# clock.net
KiCad netlist of a schematic drawn in EAGLE
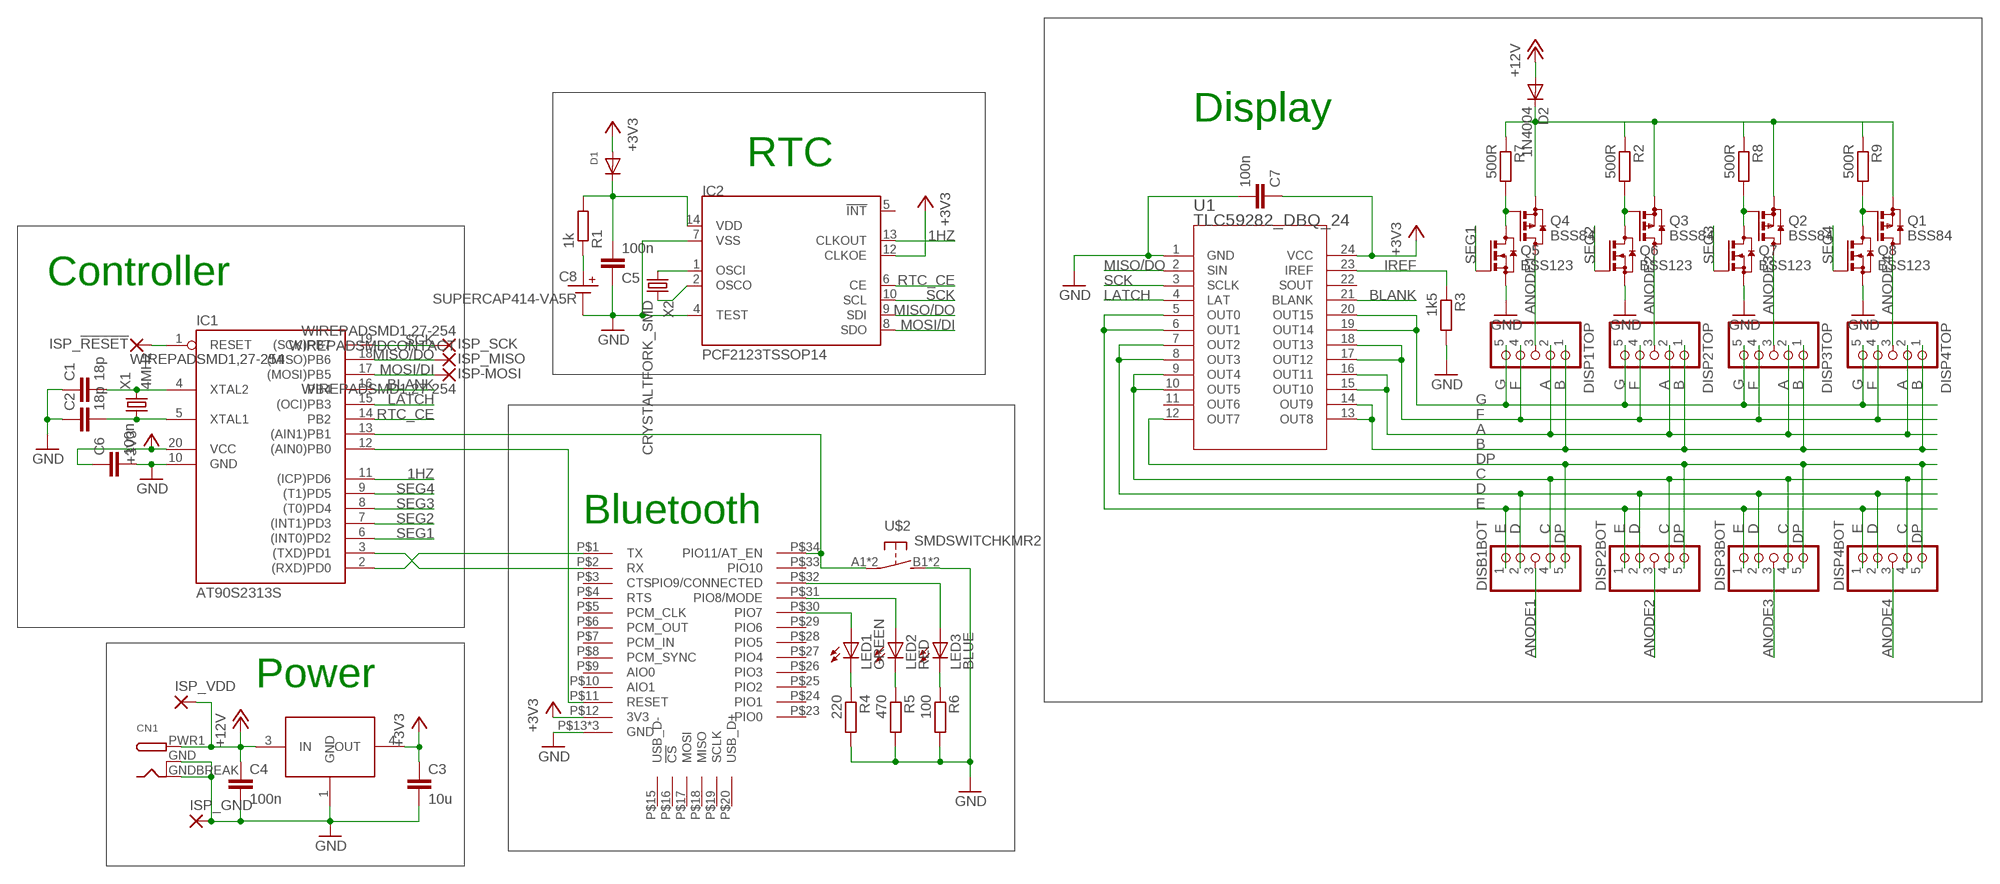
[diagram p0: schematic, sheet 1]

(export (version "E")
  (design (tool "Eeschema 10.0.6"))
  (components
    (comp (ref "C1")
      (value "18p")
      (footprint "eagle-import:C0603K")
      (libsource (lib "eagle-import") (part "C-EUC0603K"))
    )
    (comp (ref "C2")
      (value "18p")
      (footprint "eagle-import:C0603K")
      (libsource (lib "eagle-import") (part "C-EUC0603K"))
    )
    (comp (ref "C3")
      (value "10u")
      (footprint "eagle-import:C0805K")
      (libsource (lib "eagle-import") (part "C-EUC0805K"))
    )
    (comp (ref "C4")
      (value "100n")
      (footprint "eagle-import:C0603K")
      (libsource (lib "eagle-import") (part "C-EUC0603K"))
    )
    (comp (ref "C5")
      (value "100n")
      (footprint "eagle-import:C0603K")
      (libsource (lib "eagle-import") (part "C-EUC0603K"))
    )
    (comp (ref "C6")
      (value "100n")
      (footprint "eagle-import:C0603K")
      (libsource (lib "eagle-import") (part "C-EUC0603K"))
    )
    (comp (ref "C7")
      (value "100n")
      (footprint "eagle-import:C0603K")
      (libsource (lib "eagle-import") (part "C-EUC0603K"))
    )
    (comp (ref "C8")
      (value "SUPERCAP414-VA5R")
      (footprint "eagle-import:414-VA5R")
      (libsource (lib "eagle-import") (part "SUPERCAP414-VA5R"))
    )
    (comp (ref "CN1")
      (value "DCBARRELSMT")
      (footprint "eagle-import:DCJACK_2MM_SMT")
      (libsource (lib "eagle-import") (part "DCBARRELSMT"))
    )
    (comp (ref "D1")
      (value "DIODESOD-523")
      (footprint "eagle-import:SOD-523")
      (libsource (lib "eagle-import") (part "DIODESOD-523"))
    )
    (comp (ref "D2")
      (value "1N4004")
      (footprint "eagle-import:DO41-10")
      (libsource (lib "eagle-import") (part "1N4004"))
    )
    (comp (ref "DISB1BOT")
      (value "PINHD-1X5")
      (footprint "eagle-import:1X05WIDE")
      (libsource (lib "eagle-import") (part "PINHD-1X5"))
    )
    (comp (ref "DISP1TOP")
      (value "PINHD-1X5")
      (footprint "eagle-import:1X05WIDE")
      (libsource (lib "eagle-import") (part "PINHD-1X5"))
    )
    (comp (ref "DISP2BOT")
      (value "PINHD-1X5")
      (footprint "eagle-import:1X05WIDE")
      (libsource (lib "eagle-import") (part "PINHD-1X5"))
    )
    (comp (ref "DISP2TOP")
      (value "PINHD-1X5")
      (footprint "eagle-import:1X05WIDE")
      (libsource (lib "eagle-import") (part "PINHD-1X5"))
    )
    (comp (ref "DISP3BOT")
      (value "PINHD-1X5")
      (footprint "eagle-import:1X05WIDE")
      (libsource (lib "eagle-import") (part "PINHD-1X5"))
    )
    (comp (ref "DISP3TOP")
      (value "PINHD-1X5")
      (footprint "eagle-import:1X05WIDE")
      (libsource (lib "eagle-import") (part "PINHD-1X5"))
    )
    (comp (ref "DISP4BOT")
      (value "PINHD-1X5")
      (footprint "eagle-import:1X05WIDE")
      (libsource (lib "eagle-import") (part "PINHD-1X5"))
    )
    (comp (ref "DISP4TOP")
      (value "PINHD-1X5")
      (footprint "eagle-import:1X05WIDE")
      (libsource (lib "eagle-import") (part "PINHD-1X5"))
    )
    (comp (ref "IC1")
      (value "AT90S2313S")
      (footprint "eagle-import:SO20L")
      (libsource (lib "eagle-import") (part "AT90S2313S"))
    )
    (comp (ref "IC2")
      (value "PCF2123TSSOP14")
      (footprint "eagle-import:TSSOP14")
      (libsource (lib "eagle-import") (part "PCF2123TSSOP14"))
    )
    (comp (ref "ISP-MOSI")
      (value "WIREPADSMD1,27-254")
      (footprint "eagle-import:SMD1,27-2,54")
      (libsource (lib "eagle-import") (part "WIREPADSMD1,27-254"))
    )
    (comp (ref "ISP_!RESET")
      (value "WIREPADSMD1,27-254")
      (footprint "eagle-import:SMD1,27-2,54")
      (libsource (lib "eagle-import") (part "WIREPADSMD1,27-254"))
    )
    (comp (ref "ISP_GND")
      (value "WIREPADSMD2,54-2,54")
      (footprint "eagle-import:SMD2,54-2,54")
      (libsource (lib "eagle-import") (part "WIREPADSMD2,54-2,54"))
    )
    (comp (ref "ISP_MISO")
      (value "WIREPADSMDCONTACT")
      (footprint "eagle-import:SMDCONTACT")
      (libsource (lib "eagle-import") (part "WIREPADSMDCONTACT"))
    )
    (comp (ref "ISP_SCK")
      (value "WIREPADSMD1,27-254")
      (footprint "eagle-import:SMD1,27-2,54")
      (libsource (lib "eagle-import") (part "WIREPADSMD1,27-254"))
    )
    (comp (ref "ISP_VDD")
      (value "WIREPADSMD2,54-2,54")
      (footprint "eagle-import:SMD2,54-2,54")
      (libsource (lib "eagle-import") (part "WIREPADSMD2,54-2,54"))
    )
    (comp (ref "LED1")
      (value "GREEN")
      (footprint "eagle-import:CHIPLED_0805")
      (libsource (lib "eagle-import") (part "LEDCHIPLED_0805"))
    )
    (comp (ref "LED2")
      (value "RED")
      (footprint "eagle-import:CHIPLED_0805")
      (libsource (lib "eagle-import") (part "LEDCHIPLED_0805"))
    )
    (comp (ref "LED3")
      (value "BLUE")
      (footprint "eagle-import:CHIPLED_0805")
      (libsource (lib "eagle-import") (part "LEDCHIPLED_0805"))
    )
    (comp (ref "Q1")
      (value "BSS84")
      (footprint "eagle-import:SOT23")
      (libsource (lib "eagle-import") (part "BSS84"))
    )
    (comp (ref "Q2")
      (value "BSS84")
      (footprint "eagle-import:SOT23")
      (libsource (lib "eagle-import") (part "BSS84"))
    )
    (comp (ref "Q3")
      (value "BSS84")
      (footprint "eagle-import:SOT23")
      (libsource (lib "eagle-import") (part "BSS84"))
    )
    (comp (ref "Q4")
      (value "BSS84")
      (footprint "eagle-import:SOT23")
      (libsource (lib "eagle-import") (part "BSS84"))
    )
    (comp (ref "Q5")
      (value "BSS123")
      (footprint "eagle-import:SOT23")
      (libsource (lib "eagle-import") (part "BSS123"))
    )
    (comp (ref "Q6")
      (value "BSS123")
      (footprint "eagle-import:SOT23")
      (libsource (lib "eagle-import") (part "BSS123"))
    )
    (comp (ref "Q7")
      (value "BSS123")
      (footprint "eagle-import:SOT23")
      (libsource (lib "eagle-import") (part "BSS123"))
    )
    (comp (ref "Q8")
      (value "BSS123")
      (footprint "eagle-import:SOT23")
      (libsource (lib "eagle-import") (part "BSS123"))
    )
    (comp (ref "R1")
      (value "1k")
      (footprint "eagle-import:R0603")
      (libsource (lib "eagle-import") (part "R-EU_R0603"))
    )
    (comp (ref "R2")
      (value "500R")
      (footprint "eagle-import:R0603")
      (libsource (lib "eagle-import") (part "R-EU_R0603"))
    )
    (comp (ref "R3")
      (value "1k5")
      (footprint "eagle-import:R0603")
      (libsource (lib "eagle-import") (part "R-EU_R0603"))
    )
    (comp (ref "R4")
      (value "220")
      (footprint "eagle-import:R0603")
      (libsource (lib "eagle-import") (part "R-EU_R0603"))
    )
    (comp (ref "R5")
      (value "470")
      (footprint "eagle-import:R0603")
      (libsource (lib "eagle-import") (part "R-EU_R0603"))
    )
    (comp (ref "R6")
      (value "100")
      (footprint "eagle-import:R0603")
      (libsource (lib "eagle-import") (part "R-EU_R0603"))
    )
    (comp (ref "R7")
      (value "500R")
      (footprint "eagle-import:R0603")
      (libsource (lib "eagle-import") (part "R-EU_R0603"))
    )
    (comp (ref "R8")
      (value "500R")
      (footprint "eagle-import:R0603")
      (libsource (lib "eagle-import") (part "R-EU_R0603"))
    )
    (comp (ref "R9")
      (value "500R")
      (footprint "eagle-import:R0603")
      (libsource (lib "eagle-import") (part "R-EU_R0603"))
    )
    (comp (ref "U$1")
      (value "BT-HC-05")
      (footprint "eagle-import:BT-HC-05")
      (libsource (lib "eagle-import") (part "BT-HC-05"))
    )
    (comp (ref "U$2")
      (value "SMDSWITCHKMR2")
      (footprint "eagle-import:KMR2")
      (libsource (lib "eagle-import") (part "SMDSWITCHKMR2"))
    )
    (comp (ref "U$3")
      (value "REGULATORDPAK")
      (footprint "eagle-import:DPAK")
      (libsource (lib "eagle-import") (part "REGULATORDPAK"))
    )
    (comp (ref "U1")
      (value "TLC59282_DBQ_24")
      (footprint "eagle-import:DBQ24")
      (fields
        (field (name "GENERIC_PART_NUMBER") "TLC59282")
        (field (name "MANUFACTURER") "Texas Instruments")
        (field (name "MANUFACTURER_PART_NUMBER") "tlc59282_dbq_24")
      )
      (libsource (lib "eagle-import") (part "TLC59282_DBQ_24"))
    )
    (comp (ref "X1")
      (value "4MHz")
      (footprint "eagle-import:HC49UP")
      (libsource (lib "eagle-import") (part "CRYSTALHC49UP"))
    )
    (comp (ref "X2")
      (value "CRYSTALTFORK_SMD")
      (footprint "eagle-import:TFORK_SMD")
      (libsource (lib "eagle-import") (part "CRYSTALTFORK_SMD"))
    )
  )
  (nets
    (net (code "1") (name "+3V3") (class "Default")
      (node (ref "C3") (pin "1") (pinfunction "1_1") (pintype "passive"))
      (node (ref "C6") (pin "1") (pinfunction "1_1") (pintype "passive"))
      (node (ref "C7") (pin "1") (pinfunction "1_1") (pintype "passive"))
      (node (ref "D1") (pin "A") (pinfunction "A_A") (pintype "passive"))
      (node (ref "IC1") (pin "20") (pinfunction "VCC_20") (pintype "power_in"))
      (node (ref "IC2") (pin "12") (pinfunction "CLKOE_12") (pintype "input"))
      (node (ref "U$1") (pin "P$12") (pinfunction "3V3_P$12") (pintype "bidirectional"))
      (node (ref "U$3") (pin "4") (pinfunction "OUT_4") (pintype "bidirectional"))
      (node (ref "U1") (pin "24") (pinfunction "VCC_24") (pintype "power_in"))
    )
    (net (code "2") (name "+12V") (class "Default")
      (node (ref "C4") (pin "1") (pinfunction "1_1") (pintype "passive"))
      (node (ref "CN1") (pin "PWR1") (pinfunction "PWR_PWR1") (pintype "power_in"))
      (node (ref "D2") (pin "A") (pinfunction "A_A") (pintype "passive"))
      (node (ref "ISP_VDD") (pin "1") (pinfunction "P_1") (pintype "passive"))
      (node (ref "U$3") (pin "3") (pinfunction "IN_3") (pintype "bidirectional"))
    )
    (net (code "3") (name "/1HZ") (class "Default")
      (node (ref "IC1") (pin "11") (pinfunction "(ICP)PD6_11") (pintype "bidirectional"))
      (node (ref "IC2") (pin "13") (pinfunction "CLKOUT_13") (pintype "output"))
    )
    (net (code "4") (name "/A") (class "Default")
      (node (ref "DISP1TOP") (pin "2") (pinfunction "2_2") (pintype "passive"))
      (node (ref "DISP2TOP") (pin "2") (pinfunction "2_2") (pintype "passive"))
      (node (ref "DISP3TOP") (pin "2") (pinfunction "2_2") (pintype "passive"))
      (node (ref "DISP4TOP") (pin "2") (pinfunction "2_2") (pintype "passive"))
      (node (ref "U1") (pin "15") (pinfunction "OUT10_15") (pintype "output"))
      (node (ref "U1") (pin "16") (pinfunction "OUT11_16") (pintype "output"))
    )
    (net (code "5") (name "/ANODE1") (class "Default")
      (node (ref "DISB1BOT") (pin "3") (pinfunction "3_3") (pintype "passive"))
      (node (ref "DISP1TOP") (pin "3") (pinfunction "3_3") (pintype "passive"))
      (node (ref "Q4") (pin "3") (pinfunction "D_3") (pintype "passive"))
    )
    (net (code "6") (name "/ANODE2") (class "Default")
      (node (ref "DISP2BOT") (pin "3") (pinfunction "3_3") (pintype "passive"))
      (node (ref "DISP2TOP") (pin "3") (pinfunction "3_3") (pintype "passive"))
      (node (ref "Q3") (pin "3") (pinfunction "D_3") (pintype "passive"))
    )
    (net (code "7") (name "/ANODE3") (class "Default")
      (node (ref "DISP3BOT") (pin "3") (pinfunction "3_3") (pintype "passive"))
      (node (ref "DISP3TOP") (pin "3") (pinfunction "3_3") (pintype "passive"))
      (node (ref "Q2") (pin "3") (pinfunction "D_3") (pintype "passive"))
    )
    (net (code "8") (name "/ANODE4") (class "Default")
      (node (ref "DISP4BOT") (pin "3") (pinfunction "3_3") (pintype "passive"))
      (node (ref "DISP4TOP") (pin "3") (pinfunction "3_3") (pintype "passive"))
      (node (ref "Q1") (pin "3") (pinfunction "D_3") (pintype "passive"))
    )
    (net (code "9") (name "/B") (class "Default")
      (node (ref "DISP1TOP") (pin "1") (pinfunction "1_1") (pintype "passive"))
      (node (ref "DISP2TOP") (pin "1") (pinfunction "1_1") (pintype "passive"))
      (node (ref "DISP3TOP") (pin "1") (pinfunction "1_1") (pintype "passive"))
      (node (ref "DISP4TOP") (pin "1") (pinfunction "1_1") (pintype "passive"))
      (node (ref "U1") (pin "13") (pinfunction "OUT8_13") (pintype "output"))
      (node (ref "U1") (pin "14") (pinfunction "OUT9_14") (pintype "output"))
    )
    (net (code "10") (name "/BLANK") (class "Default")
      (node (ref "IC1") (pin "16") (pinfunction "PB4_16") (pintype "bidirectional"))
      (node (ref "U1") (pin "21") (pinfunction "BLANK_21") (pintype "input"))
    )
    (net (code "11") (name "/C") (class "Default")
      (node (ref "DISB1BOT") (pin "4") (pinfunction "4_4") (pintype "passive"))
      (node (ref "DISP2BOT") (pin "4") (pinfunction "4_4") (pintype "passive"))
      (node (ref "DISP3BOT") (pin "4") (pinfunction "4_4") (pintype "passive"))
      (node (ref "DISP4BOT") (pin "4") (pinfunction "4_4") (pintype "passive"))
      (node (ref "U1") (pin "10") (pinfunction "OUT5_10") (pintype "output"))
      (node (ref "U1") (pin "9") (pinfunction "OUT4_9") (pintype "output"))
    )
    (net (code "12") (name "/D") (class "Default")
      (node (ref "DISB1BOT") (pin "2") (pinfunction "2_2") (pintype "passive"))
      (node (ref "DISP2BOT") (pin "2") (pinfunction "2_2") (pintype "passive"))
      (node (ref "DISP3BOT") (pin "2") (pinfunction "2_2") (pintype "passive"))
      (node (ref "DISP4BOT") (pin "2") (pinfunction "2_2") (pintype "passive"))
      (node (ref "U1") (pin "7") (pinfunction "OUT2_7") (pintype "output"))
      (node (ref "U1") (pin "8") (pinfunction "OUT3_8") (pintype "output"))
    )
    (net (code "13") (name "/DP") (class "Default")
      (node (ref "DISB1BOT") (pin "5") (pinfunction "5_5") (pintype "passive"))
      (node (ref "DISP2BOT") (pin "5") (pinfunction "5_5") (pintype "passive"))
      (node (ref "DISP3BOT") (pin "5") (pinfunction "5_5") (pintype "passive"))
      (node (ref "DISP4BOT") (pin "5") (pinfunction "5_5") (pintype "passive"))
      (node (ref "U1") (pin "12") (pinfunction "OUT7_12") (pintype "output"))
    )
    (net (code "14") (name "/E") (class "Default")
      (node (ref "DISB1BOT") (pin "1") (pinfunction "1_1") (pintype "passive"))
      (node (ref "DISP2BOT") (pin "1") (pinfunction "1_1") (pintype "passive"))
      (node (ref "DISP3BOT") (pin "1") (pinfunction "1_1") (pintype "passive"))
      (node (ref "DISP4BOT") (pin "1") (pinfunction "1_1") (pintype "passive"))
      (node (ref "U1") (pin "5") (pinfunction "OUT0_5") (pintype "output"))
      (node (ref "U1") (pin "6") (pinfunction "OUT1_6") (pintype "output"))
    )
    (net (code "15") (name "/F") (class "Default")
      (node (ref "DISP1TOP") (pin "4") (pinfunction "4_4") (pintype "passive"))
      (node (ref "DISP2TOP") (pin "4") (pinfunction "4_4") (pintype "passive"))
      (node (ref "DISP3TOP") (pin "4") (pinfunction "4_4") (pintype "passive"))
      (node (ref "DISP4TOP") (pin "4") (pinfunction "4_4") (pintype "passive"))
      (node (ref "U1") (pin "17") (pinfunction "OUT12_17") (pintype "output"))
      (node (ref "U1") (pin "18") (pinfunction "OUT13_18") (pintype "output"))
    )
    (net (code "16") (name "/G") (class "Default")
      (node (ref "DISP1TOP") (pin "5") (pinfunction "5_5") (pintype "passive"))
      (node (ref "DISP2TOP") (pin "5") (pinfunction "5_5") (pintype "passive"))
      (node (ref "DISP3TOP") (pin "5") (pinfunction "5_5") (pintype "passive"))
      (node (ref "DISP4TOP") (pin "5") (pinfunction "5_5") (pintype "passive"))
      (node (ref "U1") (pin "19") (pinfunction "OUT14_19") (pintype "output"))
      (node (ref "U1") (pin "20") (pinfunction "OUT15_20") (pintype "output"))
    )
    (net (code "17") (name "/IREF") (class "Default")
      (node (ref "R3") (pin "1") (pinfunction "1_1") (pintype "passive"))
      (node (ref "U1") (pin "23") (pinfunction "IREF_23") (pintype "bidirectional"))
    )
    (net (code "18") (name "/LATCH") (class "Default")
      (node (ref "IC1") (pin "15") (pinfunction "(OCI)PB3_15") (pintype "bidirectional"))
      (node (ref "U1") (pin "4") (pinfunction "LAT_4") (pintype "input"))
    )
    (net (code "19") (name "/MISO{slash}DO") (class "Default")
      (node (ref "IC1") (pin "18") (pinfunction "(MISO)PB6_18") (pintype "bidirectional"))
      (node (ref "IC2") (pin "9") (pinfunction "SDI_9") (pintype "input"))
      (node (ref "ISP_MISO") (pin "1") (pinfunction "P_1") (pintype "passive"))
      (node (ref "U1") (pin "2") (pinfunction "SIN_2") (pintype "input"))
    )
    (net (code "20") (name "/MOSI{slash}DI") (class "Default")
      (node (ref "IC1") (pin "17") (pinfunction "(MOSI)PB5_17") (pintype "bidirectional"))
      (node (ref "IC2") (pin "8") (pinfunction "SDO_8") (pintype "output"))
      (node (ref "ISP-MOSI") (pin "1") (pinfunction "P_1") (pintype "passive"))
    )
    (net (code "21") (name "/RTC_CE") (class "Default")
      (node (ref "IC1") (pin "14") (pinfunction "PB2_14") (pintype "bidirectional"))
      (node (ref "IC2") (pin "6") (pinfunction "CE_6") (pintype "input"))
    )
    (net (code "22") (name "/SCK") (class "Default")
      (node (ref "IC1") (pin "19") (pinfunction "(SCK)PB7_19") (pintype "bidirectional"))
      (node (ref "IC2") (pin "10") (pinfunction "SCL_10") (pintype "input"))
      (node (ref "ISP_SCK") (pin "1") (pinfunction "P_1") (pintype "passive"))
      (node (ref "U1") (pin "3") (pinfunction "SCLK_3") (pintype "input"))
    )
    (net (code "23") (name "/SEG1") (class "Default")
      (node (ref "IC1") (pin "6") (pinfunction "(INT0)PD2_6") (pintype "bidirectional"))
      (node (ref "Q5") (pin "1") (pinfunction "G_1") (pintype "passive"))
    )
    (net (code "24") (name "/SEG2") (class "Default")
      (node (ref "IC1") (pin "7") (pinfunction "(INT1)PD3_7") (pintype "bidirectional"))
      (node (ref "Q6") (pin "1") (pinfunction "G_1") (pintype "passive"))
    )
    (net (code "25") (name "/SEG3") (class "Default")
      (node (ref "IC1") (pin "8") (pinfunction "(T0)PD4_8") (pintype "bidirectional"))
      (node (ref "Q7") (pin "1") (pinfunction "G_1") (pintype "passive"))
    )
    (net (code "26") (name "/SEG4") (class "Default")
      (node (ref "IC1") (pin "9") (pinfunction "(T1)PD5_9") (pintype "bidirectional"))
      (node (ref "Q8") (pin "1") (pinfunction "G_1") (pintype "passive"))
    )
    (net (code "27") (name "GND") (class "Default")
      (node (ref "C1") (pin "1") (pinfunction "1_1") (pintype "passive"))
      (node (ref "C2") (pin "1") (pinfunction "1_1") (pintype "passive"))
      (node (ref "C3") (pin "2") (pinfunction "2_2") (pintype "passive"))
      (node (ref "C4") (pin "2") (pinfunction "2_2") (pintype "passive"))
      (node (ref "C5") (pin "1") (pinfunction "1_1") (pintype "passive"))
      (node (ref "C6") (pin "2") (pinfunction "2_2") (pintype "passive"))
      (node (ref "C7") (pin "2") (pinfunction "2_2") (pintype "passive"))
      (node (ref "C8") (pin "MINUS") (pinfunction "MINUS_MINUS") (pintype "passive"))
      (node (ref "CN1") (pin "GND") (pinfunction "GNDBREAK_GND") (pintype "power_in"))
      (node (ref "CN1") (pin "GNDBREAK") (pinfunction "GND_GNDBREAK") (pintype "power_in"))
      (node (ref "IC1") (pin "10") (pinfunction "GND_10") (pintype "power_in"))
      (node (ref "IC2") (pin "4") (pinfunction "TEST_4") (pintype "input"))
      (node (ref "IC2") (pin "7") (pinfunction "VSS_7") (pintype "power_in"))
      (node (ref "ISP_GND") (pin "1") (pinfunction "P_1") (pintype "passive"))
      (node (ref "Q5") (pin "2") (pinfunction "S_2") (pintype "passive"))
      (node (ref "Q6") (pin "2") (pinfunction "S_2") (pintype "passive"))
      (node (ref "Q7") (pin "2") (pinfunction "S_2") (pintype "passive"))
      (node (ref "Q8") (pin "2") (pinfunction "S_2") (pintype "passive"))
      (node (ref "R3") (pin "2") (pinfunction "2_2") (pintype "passive"))
      (node (ref "R4") (pin "2") (pinfunction "2_2") (pintype "passive"))
      (node (ref "R5") (pin "2") (pinfunction "2_2") (pintype "passive"))
      (node (ref "R6") (pin "2") (pinfunction "2_2") (pintype "passive"))
      (node (ref "U$1") (pin "P$13") (pinfunction "GND_P$13") (pintype "bidirectional"))
      (node (ref "U$1") (pin "P$21") (pinfunction "GND_P$21") (pintype "bidirectional"))
      (node (ref "U$1") (pin "P$22") (pinfunction "GND_P$22") (pintype "bidirectional"))
      (node (ref "U$2") (pin "B1") (pinfunction "S_B1") (pintype "passive"))
      (node (ref "U$2") (pin "B2") (pinfunction "S_B2") (pintype "passive"))
      (node (ref "U$3") (pin "1") (pinfunction "GND_1") (pintype "bidirectional"))
      (node (ref "U1") (pin "1") (pinfunction "GND_1") (pintype "power_in"))
    )
    (net (code "28") (name "Net-(C8-PadPLUS)") (class "Default")
      (node (ref "C8") (pin "PLUS") (pinfunction "PLUS_PLUS") (pintype "passive"))
      (node (ref "R1") (pin "1") (pinfunction "1_1") (pintype "passive"))
    )
    (net (code "29") (name "Net-(D1-C)") (class "Default")
      (node (ref "C5") (pin "2") (pinfunction "2_2") (pintype "passive"))
      (node (ref "D1") (pin "K") (pinfunction "C_K") (pintype "passive"))
      (node (ref "IC2") (pin "14") (pinfunction "VDD_14") (pintype "power_in"))
      (node (ref "R1") (pin "2") (pinfunction "2_2") (pintype "passive"))
    )
    (net (code "30") (name "Net-(IC1-(AIN0)PB0)") (class "Default")
      (node (ref "IC1") (pin "12") (pinfunction "(AIN0)PB0_12") (pintype "bidirectional"))
      (node (ref "U$1") (pin "P$11") (pinfunction "RESET_P$11") (pintype "bidirectional"))
    )
    (net (code "31") (name "Net-(IC1-(AIN1)PB1)") (class "Default")
      (node (ref "IC1") (pin "13") (pinfunction "(AIN1)PB1_13") (pintype "bidirectional"))
      (node (ref "U$1") (pin "P$34") (pinfunction "PIO11/AT_EN_P$34") (pintype "bidirectional"))
      (node (ref "U$2") (pin "A1") (pinfunction "P_A1") (pintype "passive"))
      (node (ref "U$2") (pin "A2") (pinfunction "P_A2") (pintype "passive"))
    )
    (net (code "32") (name "Net-(IC1-(RXD)PD0)") (class "Default")
      (node (ref "IC1") (pin "2") (pinfunction "(RXD)PD0_2") (pintype "bidirectional"))
      (node (ref "U$1") (pin "P$1") (pinfunction "TX_P$1") (pintype "bidirectional"))
    )
    (net (code "33") (name "Net-(IC1-(TXD)PD1)") (class "Default")
      (node (ref "IC1") (pin "3") (pinfunction "(TXD)PD1_3") (pintype "bidirectional"))
      (node (ref "U$1") (pin "P$2") (pinfunction "RX_P$2") (pintype "bidirectional"))
    )
    (net (code "34") (name "Net-(IC1-RESET)") (class "Default")
      (node (ref "IC1") (pin "1") (pinfunction "RESET_1") (pintype "bidirectional"))
      (node (ref "ISP_!RESET") (pin "1") (pinfunction "P_1") (pintype "passive"))
    )
    (net (code "35") (name "Net-(IC1-XTAL1)") (class "Default")
      (node (ref "C2") (pin "2") (pinfunction "2_2") (pintype "passive"))
      (node (ref "IC1") (pin "5") (pinfunction "XTAL1_5") (pintype "bidirectional"))
      (node (ref "X1") (pin "1") (pinfunction "1_1") (pintype "passive"))
    )
    (net (code "36") (name "Net-(IC1-XTAL2)") (class "Default")
      (node (ref "C1") (pin "2") (pinfunction "2_2") (pintype "passive"))
      (node (ref "IC1") (pin "4") (pinfunction "XTAL2_4") (pintype "bidirectional"))
      (node (ref "X1") (pin "2") (pinfunction "2_2") (pintype "passive"))
    )
    (net (code "37") (name "Net-(IC2-OSCI)") (class "Default")
      (node (ref "IC2") (pin "1") (pinfunction "OSCI_1") (pintype "input"))
      (node (ref "X2") (pin "2") (pinfunction "1_2") (pintype "passive"))
    )
    (net (code "38") (name "Net-(IC2-OSCO)") (class "Default")
      (node (ref "IC2") (pin "2") (pinfunction "OSCO_2") (pintype "input"))
      (node (ref "X2") (pin "3") (pinfunction "2_3") (pintype "passive"))
    )
    (net (code "39") (name "Net-(LED1-PadC)") (class "Default")
      (node (ref "LED1") (pin "C") (pinfunction "C_C") (pintype "passive"))
      (node (ref "R4") (pin "1") (pinfunction "1_1") (pintype "passive"))
    )
    (net (code "40") (name "Net-(LED2-PadC)") (class "Default")
      (node (ref "LED2") (pin "C") (pinfunction "C_C") (pintype "passive"))
      (node (ref "R5") (pin "1") (pinfunction "1_1") (pintype "passive"))
    )
    (net (code "41") (name "Net-(LED3-PadC)") (class "Default")
      (node (ref "LED3") (pin "C") (pinfunction "C_C") (pintype "passive"))
      (node (ref "R6") (pin "1") (pinfunction "1_1") (pintype "passive"))
    )
    (net (code "42") (name "Net-(Q1-G)") (class "Default")
      (node (ref "Q1") (pin "1") (pinfunction "G_1") (pintype "passive"))
      (node (ref "Q8") (pin "3") (pinfunction "D_3") (pintype "passive"))
      (node (ref "R9") (pin "2") (pinfunction "2_2") (pintype "passive"))
    )
    (net (code "43") (name "Net-(Q1-S)") (class "Default")
      (node (ref "D2") (pin "C") (pinfunction "C_C") (pintype "passive"))
      (node (ref "Q1") (pin "2") (pinfunction "S_2") (pintype "passive"))
      (node (ref "Q2") (pin "2") (pinfunction "S_2") (pintype "passive"))
      (node (ref "Q3") (pin "2") (pinfunction "S_2") (pintype "passive"))
      (node (ref "Q4") (pin "2") (pinfunction "S_2") (pintype "passive"))
      (node (ref "R2") (pin "1") (pinfunction "1_1") (pintype "passive"))
      (node (ref "R7") (pin "1") (pinfunction "1_1") (pintype "passive"))
      (node (ref "R8") (pin "1") (pinfunction "1_1") (pintype "passive"))
      (node (ref "R9") (pin "1") (pinfunction "1_1") (pintype "passive"))
    )
    (net (code "44") (name "Net-(Q2-G)") (class "Default")
      (node (ref "Q2") (pin "1") (pinfunction "G_1") (pintype "passive"))
      (node (ref "Q7") (pin "3") (pinfunction "D_3") (pintype "passive"))
      (node (ref "R8") (pin "2") (pinfunction "2_2") (pintype "passive"))
    )
    (net (code "45") (name "Net-(Q3-G)") (class "Default")
      (node (ref "Q3") (pin "1") (pinfunction "G_1") (pintype "passive"))
      (node (ref "Q6") (pin "3") (pinfunction "D_3") (pintype "passive"))
      (node (ref "R2") (pin "2") (pinfunction "2_2") (pintype "passive"))
    )
    (net (code "46") (name "Net-(Q4-G)") (class "Default")
      (node (ref "Q4") (pin "1") (pinfunction "G_1") (pintype "passive"))
      (node (ref "Q5") (pin "3") (pinfunction "D_3") (pintype "passive"))
      (node (ref "R7") (pin "2") (pinfunction "2_2") (pintype "passive"))
    )
    (net (code "47") (name "Net-(U$1-PIO7)") (class "Default")
      (node (ref "LED1") (pin "A") (pinfunction "A_A") (pintype "passive"))
      (node (ref "U$1") (pin "P$30") (pinfunction "PIO7_P$30") (pintype "bidirectional"))
    )
    (net (code "48") (name "Net-(U$1-PIO8{slash}MODE)") (class "Default")
      (node (ref "LED2") (pin "A") (pinfunction "A_A") (pintype "passive"))
      (node (ref "U$1") (pin "P$31") (pinfunction "PIO8/MODE_P$31") (pintype "bidirectional"))
    )
    (net (code "49") (name "Net-(U$1-PIO9{slash}CONNECTED)") (class "Default")
      (node (ref "LED3") (pin "A") (pinfunction "A_A") (pintype "passive"))
      (node (ref "U$1") (pin "P$32") (pinfunction "PIO9/CONNECTED_P$32") (pintype "bidirectional"))
    )
    (net (code "50") (name "unconnected-(IC2-~{INT}-Pad5)") (class "Default")
      (node (ref "IC2") (pin "5") (pinfunction "~{INT}_5") (pintype "output"))
    )
    (net (code "51") (name "unconnected-(U$1-AIO0-PadP$9)") (class "Default")
      (node (ref "U$1") (pin "P$9") (pinfunction "AIO0_P$9") (pintype "bidirectional"))
    )
    (net (code "52") (name "unconnected-(U$1-AIO1-PadP$10)") (class "Default")
      (node (ref "U$1") (pin "P$10") (pinfunction "AIO1_P$10") (pintype "bidirectional"))
    )
    (net (code "53") (name "unconnected-(U$1-CTS-PadP$3)") (class "Default")
      (node (ref "U$1") (pin "P$3") (pinfunction "CTS_P$3") (pintype "bidirectional"))
    )
    (net (code "54") (name "unconnected-(U$1-MISO-PadP$18)") (class "Default")
      (node (ref "U$1") (pin "P$18") (pinfunction "MISO_P$18") (pintype "bidirectional"))
    )
    (net (code "55") (name "unconnected-(U$1-MOSI-PadP$17)") (class "Default")
      (node (ref "U$1") (pin "P$17") (pinfunction "MOSI_P$17") (pintype "bidirectional"))
    )
    (net (code "56") (name "unconnected-(U$1-PCM_CLK-PadP$5)") (class "Default")
      (node (ref "U$1") (pin "P$5") (pinfunction "PCM_CLK_P$5") (pintype "bidirectional"))
    )
    (net (code "57") (name "unconnected-(U$1-PCM_IN-PadP$7)") (class "Default")
      (node (ref "U$1") (pin "P$7") (pinfunction "PCM_IN_P$7") (pintype "bidirectional"))
    )
    (net (code "58") (name "unconnected-(U$1-PCM_OUT-PadP$6)") (class "Default")
      (node (ref "U$1") (pin "P$6") (pinfunction "PCM_OUT_P$6") (pintype "bidirectional"))
    )
    (net (code "59") (name "unconnected-(U$1-PCM_SYNC-PadP$8)") (class "Default")
      (node (ref "U$1") (pin "P$8") (pinfunction "PCM_SYNC_P$8") (pintype "bidirectional"))
    )
    (net (code "60") (name "unconnected-(U$1-PIO0-PadP$23)") (class "Default")
      (node (ref "U$1") (pin "P$23") (pinfunction "PIO0_P$23") (pintype "bidirectional"))
    )
    (net (code "61") (name "unconnected-(U$1-PIO1-PadP$24)") (class "Default")
      (node (ref "U$1") (pin "P$24") (pinfunction "PIO1_P$24") (pintype "bidirectional"))
    )
    (net (code "62") (name "unconnected-(U$1-PIO2-PadP$25)") (class "Default")
      (node (ref "U$1") (pin "P$25") (pinfunction "PIO2_P$25") (pintype "bidirectional"))
    )
    (net (code "63") (name "unconnected-(U$1-PIO3-PadP$26)") (class "Default")
      (node (ref "U$1") (pin "P$26") (pinfunction "PIO3_P$26") (pintype "bidirectional"))
    )
    (net (code "64") (name "unconnected-(U$1-PIO4-PadP$27)") (class "Default")
      (node (ref "U$1") (pin "P$27") (pinfunction "PIO4_P$27") (pintype "bidirectional"))
    )
    (net (code "65") (name "unconnected-(U$1-PIO5-PadP$28)") (class "Default")
      (node (ref "U$1") (pin "P$28") (pinfunction "PIO5_P$28") (pintype "bidirectional"))
    )
    (net (code "66") (name "unconnected-(U$1-PIO6-PadP$29)") (class "Default")
      (node (ref "U$1") (pin "P$29") (pinfunction "PIO6_P$29") (pintype "bidirectional"))
    )
    (net (code "67") (name "unconnected-(U$1-PIO10-PadP$33)") (class "Default")
      (node (ref "U$1") (pin "P$33") (pinfunction "PIO10_P$33") (pintype "bidirectional"))
    )
    (net (code "68") (name "unconnected-(U$1-RTS-PadP$4)") (class "Default")
      (node (ref "U$1") (pin "P$4") (pinfunction "RTS_P$4") (pintype "bidirectional"))
    )
    (net (code "69") (name "unconnected-(U$1-SCLK-PadP$19)") (class "Default")
      (node (ref "U$1") (pin "P$19") (pinfunction "SCLK_P$19") (pintype "bidirectional"))
    )
    (net (code "70") (name "unconnected-(U$1-USB_D+-PadP$20)") (class "Default")
      (node (ref "U$1") (pin "P$20") (pinfunction "USB_D+_P$20") (pintype "bidirectional"))
    )
    (net (code "71") (name "unconnected-(U$1-USB_D--PadP$15)") (class "Default")
      (node (ref "U$1") (pin "P$15") (pinfunction "USB_D-_P$15") (pintype "bidirectional"))
    )
    (net (code "72") (name "unconnected-(U$1-~{CS}-PadP$16)") (class "Default")
      (node (ref "U$1") (pin "P$16") (pinfunction "~{CS}_P$16") (pintype "bidirectional"))
    )
    (net (code "73") (name "unconnected-(U1-OUT6-Pad11)") (class "Default")
      (node (ref "U1") (pin "11") (pinfunction "OUT6_11") (pintype "output"))
    )
    (net (code "74") (name "unconnected-(U1-SOUT-Pad22)") (class "Default")
      (node (ref "U1") (pin "22") (pinfunction "SOUT_22") (pintype "output"))
    )
  )
)
